# CR78-HB.net
KiCad netlist of a schematic drawn in EAGLE
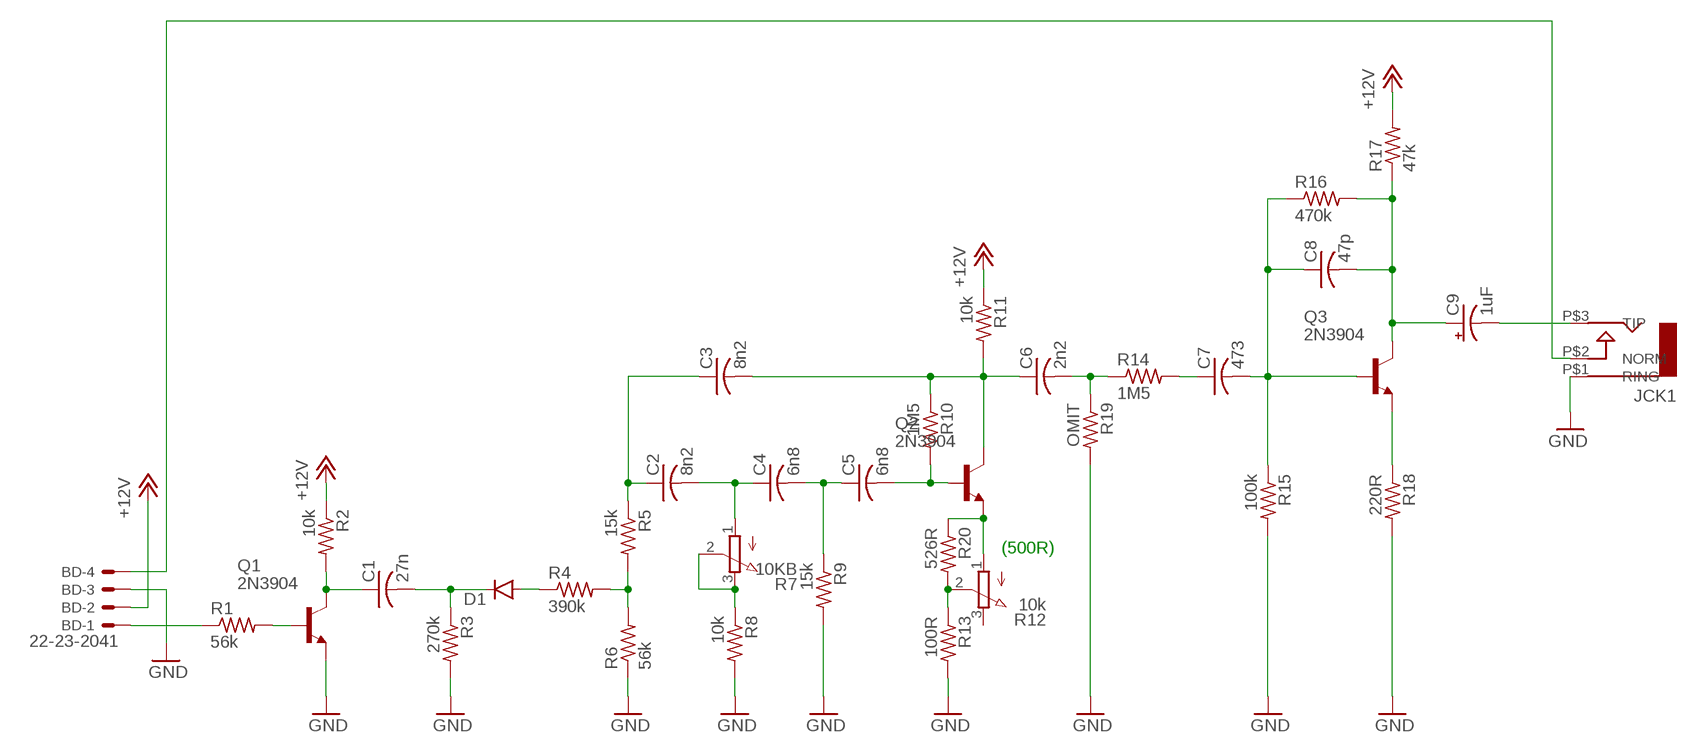
[diagram p0: schematic, sheet 1]

(export (version "E")
  (design (tool "Eeschema 10.0.6"))
  (components
    (comp (ref "BD")
      (value "22-23-2041")
      (footprint "eagle-import:22-23-2041")
      (fields (field (name "MF") "MOLEX"))
      (libsource (lib "eagle-import") (part "22-23-2041"))
    )
    (comp (ref "C1")
      (value "27n")
      (footprint "eagle-import:C050-025X075")
      (libsource (lib "eagle-import") (part "C-US050-025X075"))
    )
    (comp (ref "C2")
      (value "8n2")
      (footprint "eagle-import:C050-025X075")
      (libsource (lib "eagle-import") (part "C-US050-025X075"))
    )
    (comp (ref "C3")
      (value "8n2")
      (footprint "eagle-import:C050-025X075")
      (libsource (lib "eagle-import") (part "C-US050-025X075"))
    )
    (comp (ref "C4")
      (value "6n8")
      (footprint "eagle-import:C050-025X075")
      (libsource (lib "eagle-import") (part "C-US050-025X075"))
    )
    (comp (ref "C5")
      (value "6n8")
      (footprint "eagle-import:C050-025X075")
      (libsource (lib "eagle-import") (part "C-US050-025X075"))
    )
    (comp (ref "C6")
      (value "2n2")
      (footprint "eagle-import:C050-025X075")
      (libsource (lib "eagle-import") (part "C-US050-025X075"))
    )
    (comp (ref "C7")
      (value "473")
      (footprint "eagle-import:C050-025X075")
      (libsource (lib "eagle-import") (part "C-US050-025X075"))
    )
    (comp (ref "C8")
      (value "47p")
      (footprint "eagle-import:C050-025X075")
      (libsource (lib "eagle-import") (part "C-US050-025X075"))
    )
    (comp (ref "C9")
      (value "1uF")
      (footprint "eagle-import:B45181A")
      (libsource (lib "eagle-import") (part "CPOL-USB45181A"))
    )
    (comp (ref "D1")
      (value "DIODE1N4148")
      (footprint "eagle-import:DIODE-1N4148")
      (libsource (lib "eagle-import") (part "DIODE1N4148"))
    )
    (comp (ref "JCK1")
      (value "AUDIO-JACK")
      (footprint "eagle-import:ERTHENVAR-JACK-90DEG")
      (libsource (lib "eagle-import") (part "AUDIO-JACK"))
    )
    (comp (ref "Q1")
      (value "2N3904")
      (footprint "eagle-import:TO92")
      (libsource (lib "eagle-import") (part "2N3904"))
    )
    (comp (ref "Q2")
      (value "2N3904")
      (footprint "eagle-import:TO92")
      (libsource (lib "eagle-import") (part "2N3904"))
    )
    (comp (ref "Q3")
      (value "2N3904")
      (footprint "eagle-import:TO92")
      (libsource (lib "eagle-import") (part "2N3904"))
    )
    (comp (ref "R1")
      (value "56k")
      (footprint "eagle-import:0207_7")
      (libsource (lib "eagle-import") (part "R-US_0207/7"))
    )
    (comp (ref "R2")
      (value "10k")
      (footprint "eagle-import:0207_7")
      (libsource (lib "eagle-import") (part "R-US_0207/7"))
    )
    (comp (ref "R3")
      (value "270k")
      (footprint "eagle-import:0207_7")
      (libsource (lib "eagle-import") (part "R-US_0207/7"))
    )
    (comp (ref "R4")
      (value "390k")
      (footprint "eagle-import:0207_7")
      (libsource (lib "eagle-import") (part "R-US_0207/7"))
    )
    (comp (ref "R5")
      (value "15k")
      (footprint "eagle-import:0207_7")
      (libsource (lib "eagle-import") (part "R-US_0207/7"))
    )
    (comp (ref "R6")
      (value "56k")
      (footprint "eagle-import:0207_7")
      (libsource (lib "eagle-import") (part "R-US_0207/7"))
    )
    (comp (ref "R7")
      (value "10KB")
      (footprint "eagle-import:3RP_1610N")
      (libsource (lib "eagle-import") (part "3RP/1610N"))
    )
    (comp (ref "R8")
      (value "10k")
      (footprint "eagle-import:0207_7")
      (libsource (lib "eagle-import") (part "R-US_0207/7"))
    )
    (comp (ref "R9")
      (value "15k")
      (footprint "eagle-import:0207_5V")
      (libsource (lib "eagle-import") (part "R-US_0207/5V"))
    )
    (comp (ref "R10")
      (value "1M5")
      (footprint "eagle-import:0207_7")
      (libsource (lib "eagle-import") (part "R-US_0207/7"))
    )
    (comp (ref "R11")
      (value "10k")
      (footprint "eagle-import:0207_7")
      (libsource (lib "eagle-import") (part "R-US_0207/7"))
    )
    (comp (ref "R12")
      (value "10k")
      (footprint "eagle-import:3RP_1610N")
      (libsource (lib "eagle-import") (part "3RP/1610N"))
    )
    (comp (ref "R13")
      (value "100R")
      (footprint "eagle-import:0207_7")
      (libsource (lib "eagle-import") (part "R-US_0207/7"))
    )
    (comp (ref "R14")
      (value "1M5")
      (footprint "eagle-import:0207_7")
      (libsource (lib "eagle-import") (part "R-US_0207/7"))
    )
    (comp (ref "R15")
      (value "100k")
      (footprint "eagle-import:0207_7")
      (libsource (lib "eagle-import") (part "R-US_0207/7"))
    )
    (comp (ref "R16")
      (value "470k")
      (footprint "eagle-import:0207_7")
      (libsource (lib "eagle-import") (part "R-US_0207/7"))
    )
    (comp (ref "R17")
      (value "47k")
      (footprint "eagle-import:0207_7")
      (libsource (lib "eagle-import") (part "R-US_0207/7"))
    )
    (comp (ref "R18")
      (value "220R")
      (footprint "eagle-import:0207_7")
      (libsource (lib "eagle-import") (part "R-US_0207/7"))
    )
    (comp (ref "R19")
      (value "OMIT")
      (footprint "eagle-import:0207_5V")
      (libsource (lib "eagle-import") (part "R-US_0207/5V"))
    )
    (comp (ref "R20")
      (value "526R")
      (footprint "eagle-import:0207_5V")
      (libsource (lib "eagle-import") (part "R-US_0207/5V"))
    )
  )
  (nets
    (net (code "1") (name "+12V") (class "Default")
      (node (ref "BD") (pin "2") (pinfunction "S_2") (pintype "passive"))
      (node (ref "R11") (pin "1") (pinfunction "1_1") (pintype "passive"))
      (node (ref "R17") (pin "2") (pinfunction "2_2") (pintype "passive"))
      (node (ref "R2") (pin "1") (pinfunction "1_1") (pintype "passive"))
    )
    (net (code "2") (name "GND") (class "Default")
      (node (ref "BD") (pin "3") (pinfunction "S_3") (pintype "passive"))
      (node (ref "JCK1") (pin "P$1") (pinfunction "RING_P$1") (pintype "bidirectional"))
      (node (ref "Q1") (pin "3") (pinfunction "E_3") (pintype "passive"))
      (node (ref "R13") (pin "2") (pinfunction "2_2") (pintype "passive"))
      (node (ref "R15") (pin "2") (pinfunction "2_2") (pintype "passive"))
      (node (ref "R18") (pin "2") (pinfunction "2_2") (pintype "passive"))
      (node (ref "R19") (pin "2") (pinfunction "2_2") (pintype "passive"))
      (node (ref "R3") (pin "2") (pinfunction "2_2") (pintype "passive"))
      (node (ref "R6") (pin "1") (pinfunction "1_1") (pintype "passive"))
      (node (ref "R8") (pin "2") (pinfunction "2_2") (pintype "passive"))
      (node (ref "R9") (pin "2") (pinfunction "2_2") (pintype "passive"))
    )
    (net (code "3") (name "Net-(BDA-S)") (class "Default")
      (node (ref "BD") (pin "1") (pinfunction "S_1") (pintype "passive"))
      (node (ref "R1") (pin "1") (pinfunction "1_1") (pintype "passive"))
    )
    (net (code "4") (name "Net-(BDD-S)") (class "Default")
      (node (ref "BD") (pin "4") (pinfunction "S_4") (pintype "passive"))
      (node (ref "JCK1") (pin "P$2") (pinfunction "NORM_P$2") (pintype "bidirectional"))
    )
    (net (code "5") (name "Net-(C1-Pad2)") (class "Default")
      (node (ref "C1") (pin "2") (pinfunction "2_2") (pintype "passive"))
      (node (ref "D1") (pin "C") (pinfunction "C_C") (pintype "passive"))
      (node (ref "R3") (pin "1") (pinfunction "1_1") (pintype "passive"))
    )
    (net (code "6") (name "Net-(C2-Pad1)") (class "Default")
      (node (ref "C2") (pin "1") (pinfunction "1_1") (pintype "passive"))
      (node (ref "C3") (pin "1") (pinfunction "1_1") (pintype "passive"))
      (node (ref "R5") (pin "1") (pinfunction "1_1") (pintype "passive"))
    )
    (net (code "7") (name "Net-(C4-Pad2)") (class "Default")
      (node (ref "C4") (pin "2") (pinfunction "2_2") (pintype "passive"))
      (node (ref "C5") (pin "1") (pinfunction "1_1") (pintype "passive"))
      (node (ref "R9") (pin "1") (pinfunction "1_1") (pintype "passive"))
    )
    (net (code "8") (name "Net-(C6-Pad2)") (class "Default")
      (node (ref "C6") (pin "2") (pinfunction "2_2") (pintype "passive"))
      (node (ref "R14") (pin "1") (pinfunction "1_1") (pintype "passive"))
      (node (ref "R19") (pin "1") (pinfunction "1_1") (pintype "passive"))
    )
    (net (code "9") (name "Net-(C7-Pad1)") (class "Default")
      (node (ref "C7") (pin "1") (pinfunction "1_1") (pintype "passive"))
      (node (ref "R14") (pin "2") (pinfunction "2_2") (pintype "passive"))
    )
    (net (code "10") (name "Net-(D1-PadA)") (class "Default")
      (node (ref "D1") (pin "A") (pinfunction "A_A") (pintype "passive"))
      (node (ref "R4") (pin "1") (pinfunction "1_1") (pintype "passive"))
    )
    (net (code "11") (name "Net-(JCK1-TIP)") (class "Default")
      (node (ref "C9") (pin "-") (pinfunction "-_-") (pintype "passive"))
      (node (ref "JCK1") (pin "P$3") (pinfunction "TIP_P$3") (pintype "bidirectional"))
    )
    (net (code "12") (name "Net-(Q1-B)") (class "Default")
      (node (ref "Q1") (pin "2") (pinfunction "B_2") (pintype "passive"))
      (node (ref "R1") (pin "2") (pinfunction "2_2") (pintype "passive"))
    )
    (net (code "13") (name "Net-(Q1-C)") (class "Default")
      (node (ref "C1") (pin "1") (pinfunction "1_1") (pintype "passive"))
      (node (ref "Q1") (pin "1") (pinfunction "C_1") (pintype "passive"))
      (node (ref "R2") (pin "2") (pinfunction "2_2") (pintype "passive"))
    )
    (net (code "14") (name "Net-(Q2-B)") (class "Default")
      (node (ref "C5") (pin "2") (pinfunction "2_2") (pintype "passive"))
      (node (ref "Q2") (pin "2") (pinfunction "B_2") (pintype "passive"))
      (node (ref "R10") (pin "2") (pinfunction "2_2") (pintype "passive"))
    )
    (net (code "15") (name "Net-(Q2-C)") (class "Default")
      (node (ref "C3") (pin "2") (pinfunction "2_2") (pintype "passive"))
      (node (ref "C6") (pin "1") (pinfunction "1_1") (pintype "passive"))
      (node (ref "Q2") (pin "1") (pinfunction "C_1") (pintype "passive"))
      (node (ref "R10") (pin "1") (pinfunction "1_1") (pintype "passive"))
      (node (ref "R11") (pin "2") (pinfunction "2_2") (pintype "passive"))
    )
    (net (code "16") (name "Net-(Q2-E)") (class "Default")
      (node (ref "Q2") (pin "3") (pinfunction "E_3") (pintype "passive"))
      (node (ref "R12") (pin "1") (pinfunction "A_1") (pintype "passive"))
      (node (ref "R20") (pin "1") (pinfunction "1_1") (pintype "passive"))
    )
    (net (code "17") (name "Net-(Q3-B)") (class "Default")
      (node (ref "C7") (pin "2") (pinfunction "2_2") (pintype "passive"))
      (node (ref "C8") (pin "1") (pinfunction "1_1") (pintype "passive"))
      (node (ref "Q3") (pin "2") (pinfunction "B_2") (pintype "passive"))
      (node (ref "R15") (pin "1") (pinfunction "1_1") (pintype "passive"))
      (node (ref "R16") (pin "1") (pinfunction "1_1") (pintype "passive"))
    )
    (net (code "18") (name "Net-(Q3-C)") (class "Default")
      (node (ref "C8") (pin "2") (pinfunction "2_2") (pintype "passive"))
      (node (ref "C9") (pin "+") (pinfunction "+_+") (pintype "passive"))
      (node (ref "Q3") (pin "1") (pinfunction "C_1") (pintype "passive"))
      (node (ref "R16") (pin "2") (pinfunction "2_2") (pintype "passive"))
      (node (ref "R17") (pin "1") (pinfunction "1_1") (pintype "passive"))
    )
    (net (code "19") (name "Net-(Q3-E)") (class "Default")
      (node (ref "Q3") (pin "3") (pinfunction "E_3") (pintype "passive"))
      (node (ref "R18") (pin "1") (pinfunction "1_1") (pintype "passive"))
    )
    (net (code "20") (name "Net-(R4-Pad2)") (class "Default")
      (node (ref "R4") (pin "2") (pinfunction "2_2") (pintype "passive"))
      (node (ref "R5") (pin "2") (pinfunction "2_2") (pintype "passive"))
      (node (ref "R6") (pin "2") (pinfunction "2_2") (pintype "passive"))
    )
    (net (code "21") (name "Net-(R7-A)") (class "Default")
      (node (ref "C2") (pin "2") (pinfunction "2_2") (pintype "passive"))
      (node (ref "C4") (pin "1") (pinfunction "1_1") (pintype "passive"))
      (node (ref "R7") (pin "1") (pinfunction "A_1") (pintype "passive"))
    )
    (net (code "22") (name "Net-(R7-E)") (class "Default")
      (node (ref "R7") (pin "2") (pinfunction "S_2") (pintype "passive"))
      (node (ref "R7") (pin "3") (pinfunction "E_3") (pintype "passive"))
      (node (ref "R8") (pin "1") (pinfunction "1_1") (pintype "passive"))
    )
    (net (code "23") (name "Net-(R12-S)") (class "Default")
      (node (ref "R12") (pin "2") (pinfunction "S_2") (pintype "passive"))
      (node (ref "R13") (pin "1") (pinfunction "1_1") (pintype "passive"))
      (node (ref "R20") (pin "2") (pinfunction "2_2") (pintype "passive"))
    )
    (net (code "24") (name "unconnected-(R12-E-Pad3)") (class "Default")
      (node (ref "R12") (pin "3") (pinfunction "E_3") (pintype "passive"))
    )
  )
)
